# lv_io_harness.net
KiCad netlist of a schematic drawn in Altium Designer
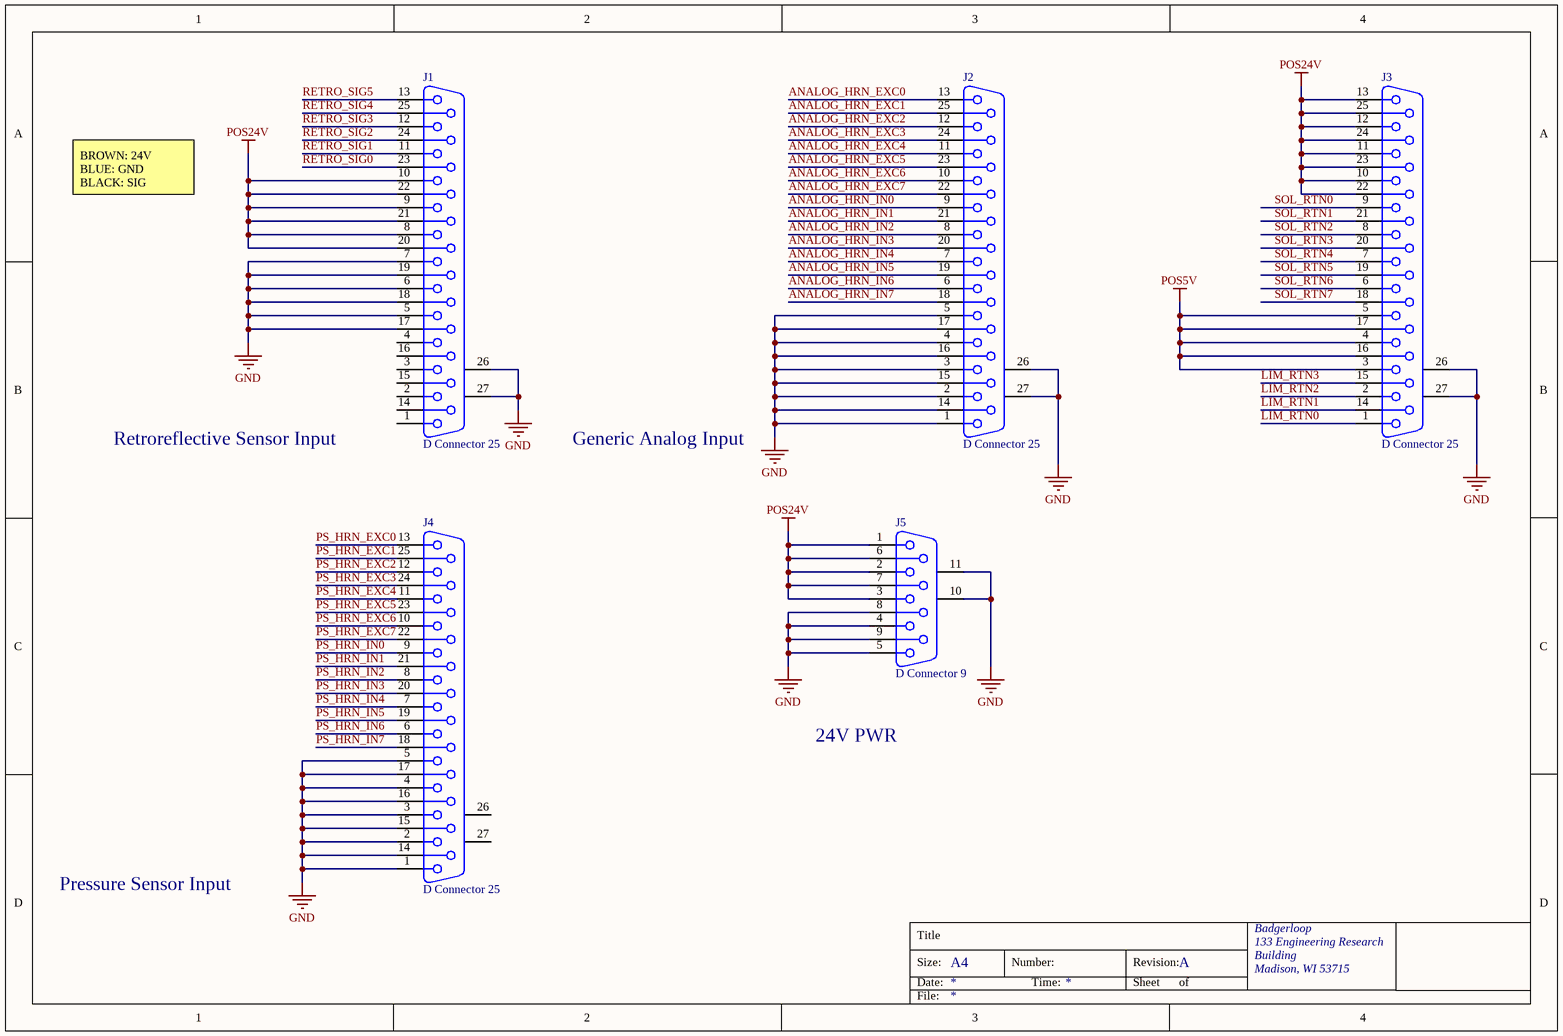
[diagram p0: lv_io_harness.SchDoc]

(export (version "E")
  (design (tool "Eeschema 10.0.6"))
  (components
    (comp (ref "J1")
      (value "D Connector 25")
      (footprint "DSUB1.385-2H25A")
      (description "Receptacle Assembly, 25 Position, Right Angle")
      (fields (field (name "PUBLISHER") "Altium Limited"))
      (libsource (lib "connector") (part "D Connector 25"))
    )
    (comp (ref "J2")
      (value "D Connector 25")
      (footprint "DSUB1.385-2H25A")
      (description "Receptacle Assembly, 25 Position, Right Angle")
      (fields (field (name "PUBLISHER") "Altium Limited"))
      (libsource (lib "connector") (part "D Connector 25"))
    )
    (comp (ref "J3")
      (value "D Connector 25")
      (footprint "DSUB1.385-2H25A")
      (description "Receptacle Assembly, 25 Position, Right Angle")
      (fields (field (name "PUBLISHER") "Altium Limited"))
      (libsource (lib "connector") (part "D Connector 25"))
    )
    (comp (ref "J4")
      (value "D Connector 25")
      (footprint "DSUB1.385-2H25A")
      (description "Receptacle Assembly, 25 Position, Right Angle")
      (fields (field (name "PUBLISHER") "Altium Limited"))
      (libsource (lib "connector") (part "D Connector 25"))
    )
    (comp (ref "J5")
      (value "D Connector 9")
      (footprint "DSUB1.385-2H9")
      (description "Receptacle Assembly, 9 Position, Right Angle")
      (fields (field (name "PUBLISHER") "Altium Limited"))
      (libsource (lib "connector") (part "D Connector 9"))
    )
  )
  (nets
    (net (code "1") (name "/ANALOG_HRN_EXC0") (class "Default")
      (node (ref "J2") (pin "13") (pinfunction "13_13") (pintype "passive"))
    )
    (net (code "2") (name "/ANALOG_HRN_EXC1") (class "Default")
      (node (ref "J2") (pin "25") (pinfunction "25_25") (pintype "passive"))
    )
    (net (code "3") (name "/ANALOG_HRN_EXC2") (class "Default")
      (node (ref "J2") (pin "12") (pinfunction "12_12") (pintype "passive"))
    )
    (net (code "4") (name "/ANALOG_HRN_EXC3") (class "Default")
      (node (ref "J2") (pin "24") (pinfunction "24_24") (pintype "passive"))
    )
    (net (code "5") (name "/ANALOG_HRN_EXC4") (class "Default")
      (node (ref "J2") (pin "11") (pinfunction "11_11") (pintype "passive"))
    )
    (net (code "6") (name "/ANALOG_HRN_EXC5") (class "Default")
      (node (ref "J2") (pin "23") (pinfunction "23_23") (pintype "passive"))
    )
    (net (code "7") (name "/ANALOG_HRN_EXC6") (class "Default")
      (node (ref "J2") (pin "10") (pinfunction "10_10") (pintype "passive"))
    )
    (net (code "8") (name "/ANALOG_HRN_EXC7") (class "Default")
      (node (ref "J2") (pin "22") (pinfunction "22_22") (pintype "passive"))
    )
    (net (code "9") (name "/ANALOG_HRN_IN0") (class "Default")
      (node (ref "J2") (pin "9") (pinfunction "9_9") (pintype "passive"))
    )
    (net (code "10") (name "/ANALOG_HRN_IN1") (class "Default")
      (node (ref "J2") (pin "21") (pinfunction "21_21") (pintype "passive"))
    )
    (net (code "11") (name "/ANALOG_HRN_IN2") (class "Default")
      (node (ref "J2") (pin "8") (pinfunction "8_8") (pintype "passive"))
    )
    (net (code "12") (name "/ANALOG_HRN_IN3") (class "Default")
      (node (ref "J2") (pin "20") (pinfunction "20_20") (pintype "passive"))
    )
    (net (code "13") (name "/ANALOG_HRN_IN4") (class "Default")
      (node (ref "J2") (pin "7") (pinfunction "7_7") (pintype "passive"))
    )
    (net (code "14") (name "/ANALOG_HRN_IN5") (class "Default")
      (node (ref "J2") (pin "19") (pinfunction "19_19") (pintype "passive"))
    )
    (net (code "15") (name "/ANALOG_HRN_IN6") (class "Default")
      (node (ref "J2") (pin "6") (pinfunction "6_6") (pintype "passive"))
    )
    (net (code "16") (name "/ANALOG_HRN_IN7") (class "Default")
      (node (ref "J2") (pin "18") (pinfunction "18_18") (pintype "passive"))
    )
    (net (code "17") (name "/LIM_RTN0") (class "Default")
      (node (ref "J3") (pin "1") (pinfunction "1_1") (pintype "passive"))
    )
    (net (code "18") (name "/LIM_RTN1") (class "Default")
      (node (ref "J3") (pin "14") (pinfunction "14_14") (pintype "passive"))
    )
    (net (code "19") (name "/LIM_RTN2") (class "Default")
      (node (ref "J3") (pin "2") (pinfunction "2_2") (pintype "passive"))
    )
    (net (code "20") (name "/LIM_RTN3") (class "Default")
      (node (ref "J3") (pin "15") (pinfunction "15_15") (pintype "passive"))
    )
    (net (code "21") (name "/PS_HRN_EXC0") (class "Default")
      (node (ref "J4") (pin "13") (pinfunction "13_13") (pintype "passive"))
    )
    (net (code "22") (name "/PS_HRN_EXC1") (class "Default")
      (node (ref "J4") (pin "25") (pinfunction "25_25") (pintype "passive"))
    )
    (net (code "23") (name "/PS_HRN_EXC2") (class "Default")
      (node (ref "J4") (pin "12") (pinfunction "12_12") (pintype "passive"))
    )
    (net (code "24") (name "/PS_HRN_EXC3") (class "Default")
      (node (ref "J4") (pin "24") (pinfunction "24_24") (pintype "passive"))
    )
    (net (code "25") (name "/PS_HRN_EXC4") (class "Default")
      (node (ref "J4") (pin "11") (pinfunction "11_11") (pintype "passive"))
    )
    (net (code "26") (name "/PS_HRN_EXC5") (class "Default")
      (node (ref "J4") (pin "23") (pinfunction "23_23") (pintype "passive"))
    )
    (net (code "27") (name "/PS_HRN_EXC6") (class "Default")
      (node (ref "J4") (pin "10") (pinfunction "10_10") (pintype "passive"))
    )
    (net (code "28") (name "/PS_HRN_EXC7") (class "Default")
      (node (ref "J4") (pin "22") (pinfunction "22_22") (pintype "passive"))
    )
    (net (code "29") (name "/PS_HRN_IN0") (class "Default")
      (node (ref "J4") (pin "9") (pinfunction "9_9") (pintype "passive"))
    )
    (net (code "30") (name "/PS_HRN_IN1") (class "Default")
      (node (ref "J4") (pin "21") (pinfunction "21_21") (pintype "passive"))
    )
    (net (code "31") (name "/PS_HRN_IN2") (class "Default")
      (node (ref "J4") (pin "8") (pinfunction "8_8") (pintype "passive"))
    )
    (net (code "32") (name "/PS_HRN_IN3") (class "Default")
      (node (ref "J4") (pin "20") (pinfunction "20_20") (pintype "passive"))
    )
    (net (code "33") (name "/PS_HRN_IN4") (class "Default")
      (node (ref "J4") (pin "7") (pinfunction "7_7") (pintype "passive"))
    )
    (net (code "34") (name "/PS_HRN_IN5") (class "Default")
      (node (ref "J4") (pin "19") (pinfunction "19_19") (pintype "passive"))
    )
    (net (code "35") (name "/PS_HRN_IN6") (class "Default")
      (node (ref "J4") (pin "6") (pinfunction "6_6") (pintype "passive"))
    )
    (net (code "36") (name "/PS_HRN_IN7") (class "Default")
      (node (ref "J4") (pin "18") (pinfunction "18_18") (pintype "passive"))
    )
    (net (code "37") (name "/RETRO_SIG0") (class "Default")
      (node (ref "J1") (pin "23") (pinfunction "23_23") (pintype "passive"))
    )
    (net (code "38") (name "/RETRO_SIG1") (class "Default")
      (node (ref "J1") (pin "11") (pinfunction "11_11") (pintype "passive"))
    )
    (net (code "39") (name "/RETRO_SIG2") (class "Default")
      (node (ref "J1") (pin "24") (pinfunction "24_24") (pintype "passive"))
    )
    (net (code "40") (name "/RETRO_SIG3") (class "Default")
      (node (ref "J1") (pin "12") (pinfunction "12_12") (pintype "passive"))
    )
    (net (code "41") (name "/RETRO_SIG4") (class "Default")
      (node (ref "J1") (pin "25") (pinfunction "25_25") (pintype "passive"))
    )
    (net (code "42") (name "/RETRO_SIG5") (class "Default")
      (node (ref "J1") (pin "13") (pinfunction "13_13") (pintype "passive"))
    )
    (net (code "43") (name "/SOL_RTN0") (class "Default")
      (node (ref "J3") (pin "9") (pinfunction "9_9") (pintype "passive"))
    )
    (net (code "44") (name "/SOL_RTN1") (class "Default")
      (node (ref "J3") (pin "21") (pinfunction "21_21") (pintype "passive"))
    )
    (net (code "45") (name "/SOL_RTN2") (class "Default")
      (node (ref "J3") (pin "8") (pinfunction "8_8") (pintype "passive"))
    )
    (net (code "46") (name "/SOL_RTN3") (class "Default")
      (node (ref "J3") (pin "20") (pinfunction "20_20") (pintype "passive"))
    )
    (net (code "47") (name "/SOL_RTN4") (class "Default")
      (node (ref "J3") (pin "7") (pinfunction "7_7") (pintype "passive"))
    )
    (net (code "48") (name "/SOL_RTN5") (class "Default")
      (node (ref "J3") (pin "19") (pinfunction "19_19") (pintype "passive"))
    )
    (net (code "49") (name "/SOL_RTN6") (class "Default")
      (node (ref "J3") (pin "6") (pinfunction "6_6") (pintype "passive"))
    )
    (net (code "50") (name "/SOL_RTN7") (class "Default")
      (node (ref "J3") (pin "18") (pinfunction "18_18") (pintype "passive"))
    )
    (net (code "51") (name "GND") (class "Default")
      (node (ref "J1") (pin "17") (pinfunction "17_17") (pintype "passive"))
      (node (ref "J1") (pin "18") (pinfunction "18_18") (pintype "passive"))
      (node (ref "J1") (pin "19") (pinfunction "19_19") (pintype "passive"))
      (node (ref "J1") (pin "26") (pinfunction "MH1_26") (pintype "passive"))
      (node (ref "J1") (pin "27") (pinfunction "MH2_27") (pintype "passive"))
      (node (ref "J1") (pin "5") (pinfunction "5_5") (pintype "passive"))
      (node (ref "J1") (pin "6") (pinfunction "6_6") (pintype "passive"))
      (node (ref "J1") (pin "7") (pinfunction "7_7") (pintype "passive"))
      (node (ref "J2") (pin "1") (pinfunction "1_1") (pintype "passive"))
      (node (ref "J2") (pin "14") (pinfunction "14_14") (pintype "passive"))
      (node (ref "J2") (pin "15") (pinfunction "15_15") (pintype "passive"))
      (node (ref "J2") (pin "16") (pinfunction "16_16") (pintype "passive"))
      (node (ref "J2") (pin "17") (pinfunction "17_17") (pintype "passive"))
      (node (ref "J2") (pin "2") (pinfunction "2_2") (pintype "passive"))
      (node (ref "J2") (pin "26") (pinfunction "MH1_26") (pintype "passive"))
      (node (ref "J2") (pin "27") (pinfunction "MH2_27") (pintype "passive"))
      (node (ref "J2") (pin "3") (pinfunction "3_3") (pintype "passive"))
      (node (ref "J2") (pin "4") (pinfunction "4_4") (pintype "passive"))
      (node (ref "J2") (pin "5") (pinfunction "5_5") (pintype "passive"))
      (node (ref "J3") (pin "26") (pinfunction "MH1_26") (pintype "passive"))
      (node (ref "J3") (pin "27") (pinfunction "MH2_27") (pintype "passive"))
      (node (ref "J4") (pin "1") (pinfunction "1_1") (pintype "passive"))
      (node (ref "J4") (pin "14") (pinfunction "14_14") (pintype "passive"))
      (node (ref "J4") (pin "15") (pinfunction "15_15") (pintype "passive"))
      (node (ref "J4") (pin "16") (pinfunction "16_16") (pintype "passive"))
      (node (ref "J4") (pin "17") (pinfunction "17_17") (pintype "passive"))
      (node (ref "J4") (pin "2") (pinfunction "2_2") (pintype "passive"))
      (node (ref "J4") (pin "3") (pinfunction "3_3") (pintype "passive"))
      (node (ref "J4") (pin "4") (pinfunction "4_4") (pintype "passive"))
      (node (ref "J4") (pin "5") (pinfunction "5_5") (pintype "passive"))
      (node (ref "J5") (pin "10") (pinfunction "MH1_10") (pintype "passive"))
      (node (ref "J5") (pin "11") (pinfunction "MH2_11") (pintype "passive"))
      (node (ref "J5") (pin "4") (pinfunction "4_4") (pintype "passive"))
      (node (ref "J5") (pin "5") (pinfunction "5_5") (pintype "passive"))
      (node (ref "J5") (pin "8") (pinfunction "8_8") (pintype "passive"))
      (node (ref "J5") (pin "9") (pinfunction "9_9") (pintype "passive"))
    )
    (net (code "52") (name "POS5V") (class "Default")
      (node (ref "J3") (pin "16") (pinfunction "16_16") (pintype "passive"))
      (node (ref "J3") (pin "17") (pinfunction "17_17") (pintype "passive"))
      (node (ref "J3") (pin "3") (pinfunction "3_3") (pintype "passive"))
      (node (ref "J3") (pin "4") (pinfunction "4_4") (pintype "passive"))
      (node (ref "J3") (pin "5") (pinfunction "5_5") (pintype "passive"))
    )
    (net (code "53") (name "POS24V") (class "Default")
      (node (ref "J1") (pin "10") (pinfunction "10_10") (pintype "passive"))
      (node (ref "J1") (pin "20") (pinfunction "20_20") (pintype "passive"))
      (node (ref "J1") (pin "21") (pinfunction "21_21") (pintype "passive"))
      (node (ref "J1") (pin "22") (pinfunction "22_22") (pintype "passive"))
      (node (ref "J1") (pin "8") (pinfunction "8_8") (pintype "passive"))
      (node (ref "J1") (pin "9") (pinfunction "9_9") (pintype "passive"))
      (node (ref "J3") (pin "10") (pinfunction "10_10") (pintype "passive"))
      (node (ref "J3") (pin "11") (pinfunction "11_11") (pintype "passive"))
      (node (ref "J3") (pin "12") (pinfunction "12_12") (pintype "passive"))
      (node (ref "J3") (pin "13") (pinfunction "13_13") (pintype "passive"))
      (node (ref "J3") (pin "22") (pinfunction "22_22") (pintype "passive"))
      (node (ref "J3") (pin "23") (pinfunction "23_23") (pintype "passive"))
      (node (ref "J3") (pin "24") (pinfunction "24_24") (pintype "passive"))
      (node (ref "J3") (pin "25") (pinfunction "25_25") (pintype "passive"))
      (node (ref "J5") (pin "1") (pinfunction "1_1") (pintype "passive"))
      (node (ref "J5") (pin "2") (pinfunction "2_2") (pintype "passive"))
      (node (ref "J5") (pin "3") (pinfunction "3_3") (pintype "passive"))
      (node (ref "J5") (pin "6") (pinfunction "6_6") (pintype "passive"))
      (node (ref "J5") (pin "7") (pinfunction "7_7") (pintype "passive"))
    )
    (net (code "54") (name "unconnected-(J1-Pad1)") (class "Default")
      (node (ref "J1") (pin "1") (pinfunction "1_1") (pintype "passive"))
    )
    (net (code "55") (name "unconnected-(J1-Pad2)") (class "Default")
      (node (ref "J1") (pin "2") (pinfunction "2_2") (pintype "passive"))
    )
    (net (code "56") (name "unconnected-(J1-Pad3)") (class "Default")
      (node (ref "J1") (pin "3") (pinfunction "3_3") (pintype "passive"))
    )
    (net (code "57") (name "unconnected-(J1-Pad4)") (class "Default")
      (node (ref "J1") (pin "4") (pinfunction "4_4") (pintype "passive"))
    )
    (net (code "58") (name "unconnected-(J1-Pad14)") (class "Default")
      (node (ref "J1") (pin "14") (pinfunction "14_14") (pintype "passive"))
    )
    (net (code "59") (name "unconnected-(J1-Pad15)") (class "Default")
      (node (ref "J1") (pin "15") (pinfunction "15_15") (pintype "passive"))
    )
    (net (code "60") (name "unconnected-(J1-Pad16)") (class "Default")
      (node (ref "J1") (pin "16") (pinfunction "16_16") (pintype "passive"))
    )
    (net (code "61") (name "unconnected-(J4-MH1-Pad26)") (class "Default")
      (node (ref "J4") (pin "26") (pinfunction "MH1_26") (pintype "passive"))
    )
    (net (code "62") (name "unconnected-(J4-MH2-Pad27)") (class "Default")
      (node (ref "J4") (pin "27") (pinfunction "MH2_27") (pintype "passive"))
    )
  )
)
